# MAIN.net
KiCad netlist of a schematic drawn in Altium Designer
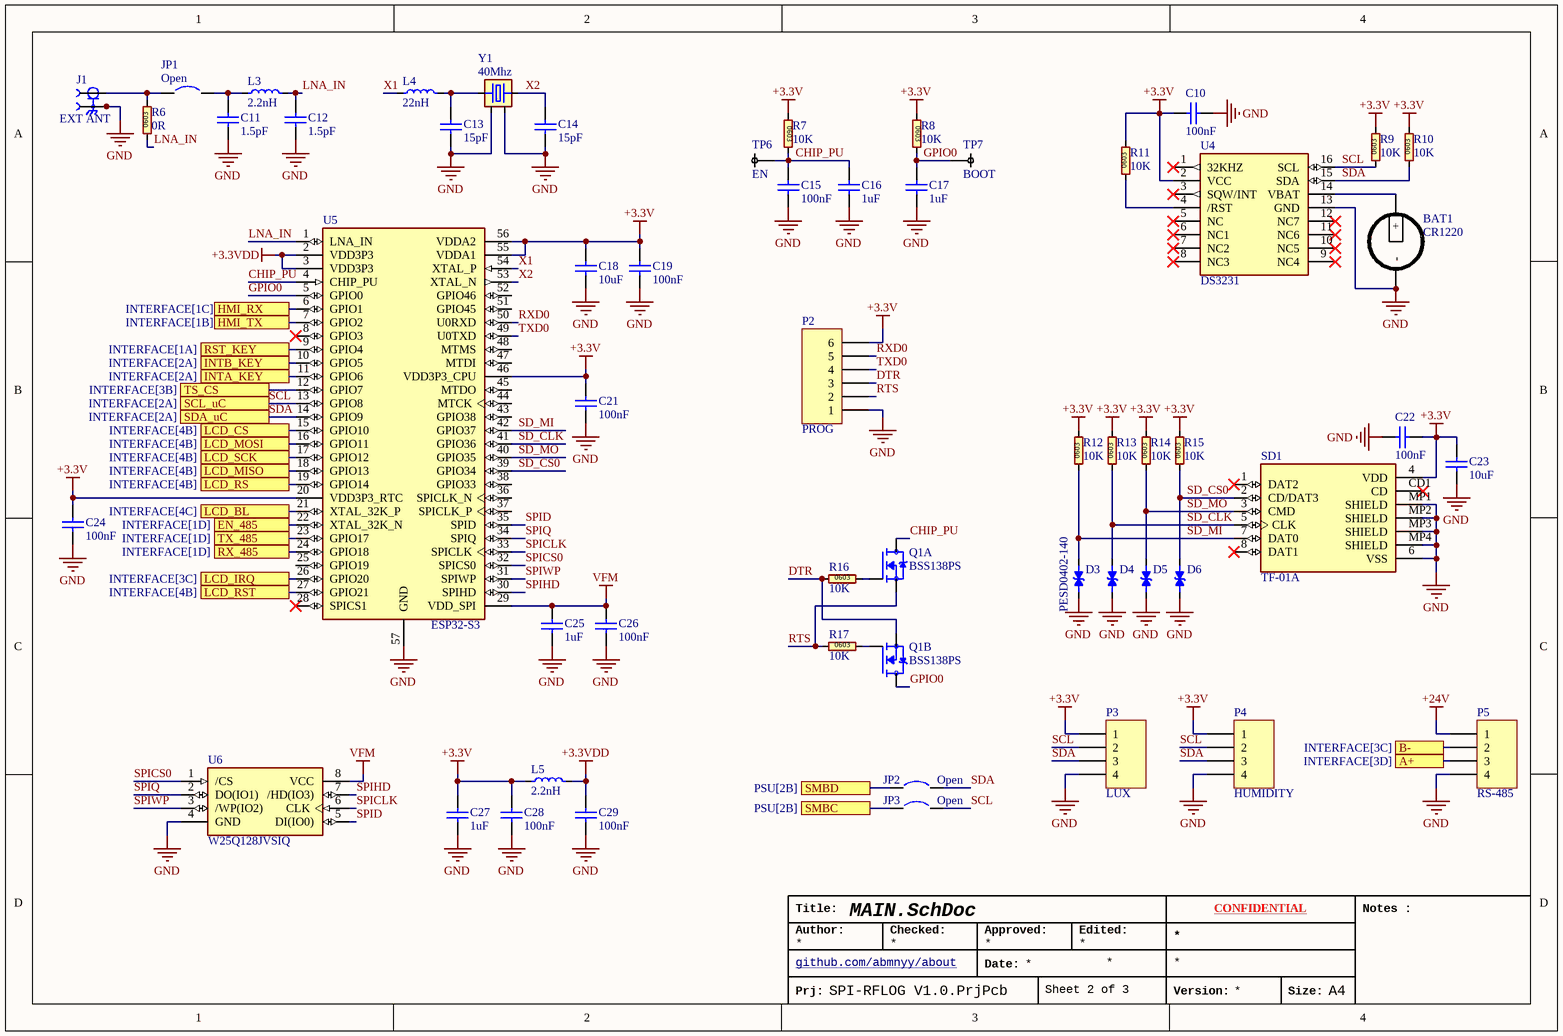
[diagram p0: MAIN.SchDoc]

(export (version "E")
  (design (tool "Eeschema 10.0.6"))
  (components
    (comp (ref "BAT1")
      (value "CR1220")
      (footprint "MPD_BC501SM-TR")
      (description "BATTERY HOLDER")
      (fields (field (name "MFR.PART #") "BC501SM") (field (name "LCSC PART #") "C5439670"))
      (libsource (lib "AB_SF") (part "CR1220 HOLDER"))
    )
    (comp (ref "C10")
      (value "100nF")
      (footprint "C0603")
      (description "0603 SMD Non-Polarity Capacitor")
      (libsource (lib "AB_SF") (part "Capacitor 0603 (Inch)"))
    )
    (comp (ref "C11")
      (value "1.5pF")
      (footprint "C0603")
      (description "0603 SMD Non-Polarity Capacitor")
      (fields (field (name "MFR.PART #") "CC0603CRNPO9BN1R5") (field (name "LCSC PART #") "C163551"))
      (libsource (lib "AB_SF") (part "Capacitor 0603 (Inch)"))
    )
    (comp (ref "C12")
      (value "1.5pF")
      (footprint "C0603")
      (description "0603 SMD Non-Polarity Capacitor")
      (fields (field (name "MFR.PART #") "CC0603CRNPO9BN1R5") (field (name "LCSC PART #") "C163551"))
      (libsource (lib "AB_SF") (part "Capacitor 0603 (Inch)"))
    )
    (comp (ref "C13")
      (value "15pF")
      (footprint "C0603")
      (description "0603 SMD Non-Polarity Capacitor")
      (fields (field (name "MFR.PART #") "X322540MPB4SI") (field (name "LCSC PART #") "C9010"))
      (libsource (lib "AB_SF") (part "Capacitor 0603 (Inch)"))
    )
    (comp (ref "C14")
      (value "15pF")
      (footprint "C0603")
      (description "0603 SMD Non-Polarity Capacitor")
      (fields (field (name "MFR.PART #") "X322540MPB4SI") (field (name "LCSC PART #") "C9010"))
      (libsource (lib "AB_SF") (part "Capacitor 0603 (Inch)"))
    )
    (comp (ref "C15")
      (value "100nF")
      (footprint "C0603")
      (description "0603 SMD Non-Polarity Capacitor")
      (libsource (lib "AB_SF") (part "Capacitor 0603 (Inch)"))
    )
    (comp (ref "C16")
      (value "1uF")
      (footprint "C0603")
      (description "0603 SMD Non-Polarity Capacitor")
      (fields (field (name "MFR.PART #") "CC0603KRX7R7BB105") (field (name "LCSC PART #") "C106248"))
      (libsource (lib "AB_SF") (part "Capacitor 0603 (Inch)"))
    )
    (comp (ref "C17")
      (value "1uF")
      (footprint "C0603")
      (description "0603 SMD Non-Polarity Capacitor")
      (fields (field (name "MFR.PART #") "CC0603KRX7R7BB105") (field (name "LCSC PART #") "C106248"))
      (libsource (lib "AB_SF") (part "Capacitor 0603 (Inch)"))
    )
    (comp (ref "C18")
      (value "10uF")
      (footprint "C0603")
      (description "0603 SMD Non-Polarity Capacitor")
      (fields (field (name "MFR.PART #") "CC0603MRX5R7BB106") (field (name "LCSC PART #") "C109457"))
      (libsource (lib "AB_SF") (part "Capacitor 0603 (Inch)"))
    )
    (comp (ref "C19")
      (value "100nF")
      (footprint "C0603")
      (description "0603 SMD Non-Polarity Capacitor")
      (libsource (lib "AB_SF") (part "Capacitor 0603 (Inch)"))
    )
    (comp (ref "C21")
      (value "100nF")
      (footprint "C0603")
      (description "0603 SMD Non-Polarity Capacitor")
      (libsource (lib "AB_SF") (part "Capacitor 0603 (Inch)"))
    )
    (comp (ref "C22")
      (value "100nF")
      (footprint "C0603")
      (description "0603 SMD Non-Polarity Capacitor")
      (libsource (lib "AB_SF") (part "Capacitor 0603 (Inch)"))
    )
    (comp (ref "C23")
      (value "10uF")
      (footprint "C0603")
      (description "0603 SMD Non-Polarity Capacitor")
      (libsource (lib "AB_SF") (part "Capacitor 0603 (Inch)"))
    )
    (comp (ref "C24")
      (value "100nF")
      (footprint "C0603")
      (description "0603 SMD Non-Polarity Capacitor")
      (libsource (lib "AB_SF") (part "Capacitor 0603 (Inch)"))
    )
    (comp (ref "C25")
      (value "1uF")
      (footprint "C0603")
      (description "0603 SMD Non-Polarity Capacitor")
      (libsource (lib "AB_SF") (part "Capacitor 0603 (Inch)"))
    )
    (comp (ref "C26")
      (value "100nF")
      (footprint "C0603")
      (description "0603 SMD Non-Polarity Capacitor")
      (libsource (lib "AB_SF") (part "Capacitor 0603 (Inch)"))
    )
    (comp (ref "C27")
      (value "1uF")
      (footprint "C0603")
      (description "0603 SMD Non-Polarity Capacitor")
      (libsource (lib "AB_SF") (part "Capacitor 0603 (Inch)"))
    )
    (comp (ref "C28")
      (value "100nF")
      (footprint "C0603")
      (description "0603 SMD Non-Polarity Capacitor")
      (libsource (lib "AB_SF") (part "Capacitor 0603 (Inch)"))
    )
    (comp (ref "C29")
      (value "100nF")
      (footprint "C0603")
      (description "0603 SMD Non-Polarity Capacitor")
      (libsource (lib "AB_SF") (part "Capacitor 0603 (Inch)"))
    )
    (comp (ref "D3")
      (value "PESD0402-140")
      (footprint "ESD0402")
      (description "40V Bidirectional 14V 0402 ESD and Surge Protection (TVS/ESD) ROHS")
      (fields (field (name "LCSC PART #") "C10662"))
      (libsource (lib "AB_SF") (part "PESD0402-140"))
    )
    (comp (ref "D4")
      (value "PESD0402-140")
      (footprint "ESD0402")
      (description "40V Bidirectional 14V 0402 ESD and Surge Protection (TVS/ESD) ROHS")
      (fields (field (name "LCSC PART #") "C10662"))
      (libsource (lib "AB_SF") (part "PESD0402-140"))
    )
    (comp (ref "D5")
      (value "PESD0402-140")
      (footprint "ESD0402")
      (description "40V Bidirectional 14V 0402 ESD and Surge Protection (TVS/ESD) ROHS")
      (fields (field (name "LCSC PART #") "C10662"))
      (libsource (lib "AB_SF") (part "PESD0402-140"))
    )
    (comp (ref "D6")
      (value "PESD0402-140")
      (footprint "ESD0402")
      (description "40V Bidirectional 14V 0402 ESD and Surge Protection (TVS/ESD) ROHS")
      (fields (field (name "LCSC PART #") "C10662"))
      (libsource (lib "AB_SF") (part "PESD0402-140"))
    )
    (comp (ref "J1")
      (value "EXT ANT")
      (footprint "IPEX_UF.L")
      (fields (field (name "MFR.PART #") "KH-IPEX-K501-29") (field (name "LCSC PART #") "C411563"))
      (libsource (lib "AB_SF") (part "IPEX UF.L"))
    )
    (comp (ref "JP1")
      (value "Open")
      (footprint "SB_STM")
      (description "Jumper Solder Pad")
      (fields (field (name "PUBLISHER") "Altium Limited"))
      (libsource (lib "AB_SF") (part "Jumper Solder"))
    )
    (comp (ref "JP2")
      (value "Open")
      (footprint "SB_STM")
      (description "Jumper Solder Pad")
      (fields (field (name "PUBLISHER") "Altium Limited"))
      (libsource (lib "AB_SF") (part "Jumper Solder"))
    )
    (comp (ref "JP3")
      (value "Open")
      (footprint "SB_STM")
      (description "Jumper Solder Pad")
      (fields (field (name "PUBLISHER") "Altium Limited"))
      (libsource (lib "AB_SF") (part "Jumper Solder"))
    )
    (comp (ref "L3")
      (value "2.2nH")
      (footprint "L0603")
      (description "Inductor with Package: 0603 Inch")
      (libsource (lib "AB_SF") (part "INDUCTOR 0603"))
    )
    (comp (ref "L4")
      (value "22nH")
      (footprint "L0603")
      (description "Inductor with Package: 0603 Inch")
      (fields (field (name "MFR.PART #") "VHF160808H22NJT") (field (name "LCSC PART #") "C90207"))
      (libsource (lib "AB_SF") (part "INDUCTOR 0603"))
    )
    (comp (ref "L5")
      (value "2.2nH")
      (footprint "L0603")
      (description "Inductor with Package: 0603 Inch")
      (fields (field (name "MFR.PART #") "LQW18AN2N2C80D") (field (name "LCSC PART #") "C71648"))
      (libsource (lib "AB_SF") (part "INDUCTOR 0603"))
    )
    (comp (ref "P2")
      (value "PROG")
      (footprint "HDR-6P-2.54mm")
      (description "Header, 6-Pin")
      (fields (field (name "PUBLISHER") "Altium Limited"))
      (libsource (lib "AB_SF") (part "Header 6"))
    )
    (comp (ref "P3")
      (value "LUX")
      (footprint "JST_XH-2.54")
      (description "CONNECTOR HEADER")
      (fields (field (name "PUBLISHER") "Altium Limited"))
      (libsource (lib "AB_SF") (part "Connector 4P"))
    )
    (comp (ref "P4")
      (value "HUMIDITY")
      (footprint "JST_XH-2.54")
      (description "CONNECTOR HEADER")
      (fields (field (name "PUBLISHER") "Altium Limited"))
      (libsource (lib "AB_SF") (part "Connector 4P"))
    )
    (comp (ref "P5")
      (value "RS-485")
      (footprint "JST_XH-2.54")
      (description "CONNECTOR HEADER")
      (fields (field (name "PUBLISHER") "Altium Limited"))
      (libsource (lib "AB_SF") (part "Connector 4P"))
    )
    (comp (ref "Q1")
      (value "BSS138PS")
      (footprint "SOT-363")
      (description "60 V, 320 mA dual N-channel Trench MOSFET")
      (fields (field (name "MFR.PART #") "BSS138PS,115") (field (name "LCSC PART #") "C193381"))
      (libsource (lib "AB_SF") (part "BSS138PS"))
    )
    (comp (ref "R6")
      (value "0R")
      (footprint "R0603")
      (description "0603 SMD Thick Resistor")
      (fields (field (name "MFR.PART #") "AC0603FR-070RL") (field (name "LCSC PART #") "C116699"))
      (libsource (lib "") (part "Resistor 0603 (Inch)_1"))
    )
    (comp (ref "R7")
      (value "10K")
      (footprint "R0603")
      (description "0603 SMD Thick Resistor")
      (libsource (lib "AB_SF") (part "Resistor 0603 (Inch)"))
    )
    (comp (ref "R8")
      (value "10K")
      (footprint "R0603")
      (description "0603 SMD Thick Resistor")
      (libsource (lib "AB_SF") (part "Resistor 0603 (Inch)"))
    )
    (comp (ref "R9")
      (value "10K")
      (footprint "R0603")
      (description "0603 SMD Thick Resistor")
      (libsource (lib "") (part "Resistor 0603 (Inch)_1"))
    )
    (comp (ref "R10")
      (value "10K")
      (footprint "R0603")
      (description "0603 SMD Thick Resistor")
      (libsource (lib "") (part "Resistor 0603 (Inch)_1"))
    )
    (comp (ref "R11")
      (value "10K")
      (footprint "R0603")
      (description "0603 SMD Thick Resistor")
      (libsource (lib "") (part "Resistor 0603 (Inch)_1"))
    )
    (comp (ref "R12")
      (value "10K")
      (footprint "R0603")
      (description "0603 SMD Thick Resistor")
      (libsource (lib "") (part "Resistor 0603 (Inch)_1"))
    )
    (comp (ref "R13")
      (value "10K")
      (footprint "R0603")
      (description "0603 SMD Thick Resistor")
      (libsource (lib "") (part "Resistor 0603 (Inch)_1"))
    )
    (comp (ref "R14")
      (value "10K")
      (footprint "R0603")
      (description "0603 SMD Thick Resistor")
      (libsource (lib "") (part "Resistor 0603 (Inch)_1"))
    )
    (comp (ref "R15")
      (value "10K")
      (footprint "R0603")
      (description "0603 SMD Thick Resistor")
      (libsource (lib "") (part "Resistor 0603 (Inch)_1"))
    )
    (comp (ref "R16")
      (value "10K")
      (footprint "R0603")
      (description "0603 SMD Thick Resistor")
      (libsource (lib "") (part "Resistor 0603 (Inch)_2"))
    )
    (comp (ref "R17")
      (value "10K")
      (footprint "R0603")
      (description "0603 SMD Thick Resistor")
      (libsource (lib "") (part "Resistor 0603 (Inch)_2"))
    )
    (comp (ref "SD1")
      (value "TF-01A")
      (footprint "TF-01A")
      (description "Standard Card Edge Connectors")
      (fields (field (name "LCSC PART #") "C2889258"))
      (libsource (lib "AB_SF") (part "TF-01A"))
    )
    (comp (ref "TP6")
      (value "EN")
      (footprint "PAD")
      (description "Thick Pad")
      (libsource (lib "AB_SF") (part "Test Point"))
    )
    (comp (ref "TP7")
      (value "BOOT")
      (footprint "PAD")
      (description "Thick Pad")
      (libsource (lib "AB_SF") (part "Test Point"))
    )
    (comp (ref "U4")
      (value "DS3231")
      (footprint "SOIC-16-WIDE")
      (description "Real Time Clock (RTC) IC Clock/Calendar - IÂ²C, 2-Wire Serial 8-SOIC (0.154, 3.90mm Width)")
      (fields (field (name "MFR.PART #") "DS3231SN#T&R") (field (name "LCSC PART #") "C9866"))
      (libsource (lib "AB_SF") (part "DS3231"))
    )
    (comp (ref "U5")
      (value "ESP32-S3")
      (footprint "ESP32-S3")
      (fields (field (name "MFR.PART #") "ESP32-S3R8") (field (name "LCSC PART #") "C2913194"))
      (libsource (lib "AB_SF") (part "ESP32-S3"))
    )
    (comp (ref "U6")
      (value "W25Q128JVSIQ")
      (footprint "SOIC-8-208miL")
      (description "FLASH - NOR Memory IC 128Mb (16M x 8) SPI - Quad I/O, QPI, DTR 133 MHz 8-SOIC")
      (fields (field (name "LCSC PART #") "C97521"))
      (libsource (lib "AB_SF") (part "W25Q128JVSIQ"))
    )
    (comp (ref "Y1")
      (value "40Mhz")
      (footprint "OSC_SMD3225-4")
      (description "40MHz Crystal Oscillator 15pF ±10ppm ±20ppm SMD3225-4P Crystals ROHS")
      (fields (field (name "MFR.PART #") "X322540MPB4SI") (field (name "LCSC PART #") "C9010"))
      (libsource (lib "AB_SF") (part "XTAL-40Mhz"))
    )
  )
  (nets
    (net (code "1") (name "+3.3V") (class "Default")
      (node (ref "C10") (pin "2") (pinfunction "2_2") (pintype "passive"))
      (node (ref "C18") (pin "2") (pinfunction "2_2") (pintype "passive"))
      (node (ref "C19") (pin "2") (pinfunction "2_2") (pintype "passive"))
      (node (ref "C21") (pin "2") (pinfunction "2_2") (pintype "passive"))
      (node (ref "C22") (pin "1") (pinfunction "1_1") (pintype "passive"))
      (node (ref "C23") (pin "2") (pinfunction "2_2") (pintype "passive"))
      (node (ref "C24") (pin "2") (pinfunction "2_2") (pintype "passive"))
      (node (ref "C27") (pin "2") (pinfunction "2_2") (pintype "passive"))
      (node (ref "C28") (pin "2") (pinfunction "2_2") (pintype "passive"))
      (node (ref "L5") (pin "1") (pinfunction "1_1") (pintype "passive"))
      (node (ref "P2") (pin "6") (pinfunction "6_6") (pintype "passive"))
      (node (ref "P3") (pin "1") (pinfunction "1_1") (pintype "passive"))
      (node (ref "P4") (pin "1") (pinfunction "1_1") (pintype "passive"))
      (node (ref "R10") (pin "2") (pinfunction "2_2") (pintype "passive"))
      (node (ref "R11") (pin "2") (pinfunction "2_2") (pintype "passive"))
      (node (ref "R12") (pin "2") (pinfunction "2_2") (pintype "passive"))
      (node (ref "R13") (pin "2") (pinfunction "2_2") (pintype "passive"))
      (node (ref "R14") (pin "2") (pinfunction "2_2") (pintype "passive"))
      (node (ref "R15") (pin "2") (pinfunction "2_2") (pintype "passive"))
      (node (ref "R7") (pin "1") (pinfunction "1_1") (pintype "passive"))
      (node (ref "R8") (pin "1") (pinfunction "1_1") (pintype "passive"))
      (node (ref "R9") (pin "2") (pinfunction "2_2") (pintype "passive"))
      (node (ref "SD1") (pin "4") (pinfunction "VDD_4") (pintype "power_in"))
      (node (ref "U4") (pin "2") (pinfunction "VCC_2") (pintype "power_in"))
      (node (ref "U5") (pin "20") (pinfunction "VDD3P3_RTC_20") (pintype "power_in"))
      (node (ref "U5") (pin "46") (pinfunction "VDD3P3_CPU_46") (pintype "power_in"))
      (node (ref "U5") (pin "55") (pinfunction "VDDA1_55") (pintype "power_in"))
      (node (ref "U5") (pin "56") (pinfunction "VDDA2_56") (pintype "power_in"))
    )
    (net (code "2") (name "+3.3VDD") (class "Default")
      (node (ref "C29") (pin "2") (pinfunction "2_2") (pintype "passive"))
      (node (ref "L5") (pin "2") (pinfunction "2_2") (pintype "passive"))
      (node (ref "U5") (pin "2") (pinfunction "VDD3P3_2") (pintype "power_in"))
      (node (ref "U5") (pin "3") (pinfunction "VDD3P3_3") (pintype "power_in"))
    )
    (net (code "3") (name "+24V") (class "Default")
      (node (ref "P5") (pin "1") (pinfunction "1_1") (pintype "passive"))
    )
    (net (code "4") (name "/A+") (class "Default")
      (node (ref "P5") (pin "3") (pinfunction "3_3") (pintype "passive"))
    )
    (net (code "5") (name "/B-") (class "Default")
      (node (ref "P5") (pin "2") (pinfunction "2_2") (pintype "passive"))
    )
    (net (code "6") (name "/CHIP_PU") (class "Default")
      (node (ref "C15") (pin "1") (pinfunction "1_1") (pintype "passive"))
      (node (ref "C16") (pin "1") (pinfunction "1_1") (pintype "passive"))
      (node (ref "Q1") (pin "6") (pinfunction "D1_6") (pintype "passive"))
      (node (ref "R7") (pin "2") (pinfunction "2_2") (pintype "passive"))
      (node (ref "TP6") (pin "1") (pinfunction "1_1") (pintype "passive"))
      (node (ref "U5") (pin "4") (pinfunction "CHIP_PU_4") (pintype "input"))
    )
    (net (code "7") (name "/DTR") (class "Default")
      (node (ref "P2") (pin "3") (pinfunction "3_3") (pintype "passive"))
      (node (ref "Q1") (pin "4") (pinfunction "S2_4") (pintype "passive"))
      (node (ref "R16") (pin "1") (pinfunction "1_1") (pintype "passive"))
    )
    (net (code "8") (name "/EN_485") (class "Default")
      (node (ref "U5") (pin "22") (pinfunction "XTAL_32K_N_22") (pintype "bidirectional"))
    )
    (net (code "9") (name "/GPIO0") (class "Default")
      (node (ref "C17") (pin "1") (pinfunction "1_1") (pintype "passive"))
      (node (ref "Q1") (pin "3") (pinfunction "D2_3") (pintype "passive"))
      (node (ref "R8") (pin "2") (pinfunction "2_2") (pintype "passive"))
      (node (ref "TP7") (pin "1") (pinfunction "1_1") (pintype "passive"))
      (node (ref "U5") (pin "5") (pinfunction "GPIO0_5") (pintype "bidirectional"))
    )
    (net (code "10") (name "/HMI_RX") (class "Default")
      (node (ref "U5") (pin "6") (pinfunction "GPIO1_6") (pintype "bidirectional"))
    )
    (net (code "11") (name "/HMI_TX") (class "Default")
      (node (ref "U5") (pin "7") (pinfunction "GPIO2_7") (pintype "bidirectional"))
    )
    (net (code "12") (name "/INTA_KEY") (class "Default")
      (node (ref "U5") (pin "11") (pinfunction "GPIO6_11") (pintype "bidirectional"))
    )
    (net (code "13") (name "/INTB_KEY") (class "Default")
      (node (ref "U5") (pin "10") (pinfunction "GPIO5_10") (pintype "bidirectional"))
    )
    (net (code "14") (name "/LCD_BL") (class "Default")
      (node (ref "U5") (pin "21") (pinfunction "XTAL_32K_P_21") (pintype "bidirectional"))
    )
    (net (code "15") (name "/LCD_CS") (class "Default")
      (node (ref "U5") (pin "15") (pinfunction "GPIO10_15") (pintype "bidirectional"))
    )
    (net (code "16") (name "/LCD_IRQ") (class "Default")
      (node (ref "U5") (pin "26") (pinfunction "GPIO20_26") (pintype "bidirectional"))
    )
    (net (code "17") (name "/LCD_MISO") (class "Default")
      (node (ref "U5") (pin "18") (pinfunction "GPIO13_18") (pintype "bidirectional"))
    )
    (net (code "18") (name "/LCD_MOSI") (class "Default")
      (node (ref "U5") (pin "16") (pinfunction "GPIO11_16") (pintype "bidirectional"))
    )
    (net (code "19") (name "/LCD_RS") (class "Default")
      (node (ref "U5") (pin "19") (pinfunction "GPIO14_19") (pintype "bidirectional"))
    )
    (net (code "20") (name "/LCD_RST") (class "Default")
      (node (ref "U5") (pin "27") (pinfunction "GPIO21_27") (pintype "bidirectional"))
    )
    (net (code "21") (name "/LCD_SCK") (class "Default")
      (node (ref "U5") (pin "17") (pinfunction "GPIO12_17") (pintype "bidirectional"))
    )
    (net (code "22") (name "/LNA_IN") (class "Default")
      (node (ref "C12") (pin "2") (pinfunction "2_2") (pintype "passive"))
      (node (ref "L3") (pin "2") (pinfunction "2_2") (pintype "passive"))
      (node (ref "R6") (pin "1") (pinfunction "1_1") (pintype "passive"))
      (node (ref "U5") (pin "1") (pinfunction "LNA_IN_1") (pintype "bidirectional"))
    )
    (net (code "23") (name "/RST_KEY") (class "Default")
      (node (ref "U5") (pin "9") (pinfunction "GPIO4_9") (pintype "bidirectional"))
    )
    (net (code "24") (name "/RTS") (class "Default")
      (node (ref "P2") (pin "2") (pinfunction "2_2") (pintype "passive"))
      (node (ref "Q1") (pin "1") (pinfunction "S1_1") (pintype "passive"))
      (node (ref "R17") (pin "1") (pinfunction "1_1") (pintype "passive"))
    )
    (net (code "25") (name "/RXD0") (class "Default")
      (node (ref "P2") (pin "5") (pinfunction "5_5") (pintype "passive"))
      (node (ref "U5") (pin "50") (pinfunction "U0RXD_50") (pintype "bidirectional"))
    )
    (net (code "26") (name "/RX_485") (class "Default")
      (node (ref "U5") (pin "24") (pinfunction "GPIO18_24") (pintype "bidirectional"))
    )
    (net (code "27") (name "/SCL") (class "Default")
      (node (ref "JP3") (pin "2") (pinfunction "2_2") (pintype "passive"))
      (node (ref "P3") (pin "2") (pinfunction "2_2") (pintype "passive"))
      (node (ref "P4") (pin "2") (pinfunction "2_2") (pintype "passive"))
      (node (ref "R9") (pin "1") (pinfunction "1_1") (pintype "passive"))
      (node (ref "U4") (pin "16") (pinfunction "SCL_16") (pintype "bidirectional"))
      (node (ref "U5") (pin "13") (pinfunction "GPIO8_13") (pintype "bidirectional"))
    )
    (net (code "28") (name "/SDA") (class "Default")
      (node (ref "JP2") (pin "2") (pinfunction "2_2") (pintype "passive"))
      (node (ref "P3") (pin "3") (pinfunction "3_3") (pintype "passive"))
      (node (ref "P4") (pin "3") (pinfunction "3_3") (pintype "passive"))
      (node (ref "R10") (pin "1") (pinfunction "1_1") (pintype "passive"))
      (node (ref "U4") (pin "15") (pinfunction "SDA_15") (pintype "bidirectional"))
      (node (ref "U5") (pin "14") (pinfunction "GPIO9_14") (pintype "bidirectional"))
    )
    (net (code "29") (name "/SD_CLK") (class "Default")
      (node (ref "D4") (pin "2") (pinfunction "2_2") (pintype "passive"))
      (node (ref "R13") (pin "1") (pinfunction "1_1") (pintype "passive"))
      (node (ref "SD1") (pin "5") (pinfunction "CLK_5") (pintype "bidirectional"))
      (node (ref "U5") (pin "41") (pinfunction "GPIO36_41") (pintype "bidirectional"))
    )
    (net (code "30") (name "/SD_CS0") (class "Default")
      (node (ref "D6") (pin "2") (pinfunction "2_2") (pintype "passive"))
      (node (ref "R15") (pin "1") (pinfunction "1_1") (pintype "passive"))
      (node (ref "SD1") (pin "2") (pinfunction "CD/DAT3_2") (pintype "bidirectional"))
      (node (ref "U5") (pin "39") (pinfunction "GPIO34_39") (pintype "bidirectional"))
    )
    (net (code "31") (name "/SD_MI") (class "Default")
      (node (ref "D3") (pin "2") (pinfunction "2_2") (pintype "passive"))
      (node (ref "R12") (pin "1") (pinfunction "1_1") (pintype "passive"))
      (node (ref "SD1") (pin "7") (pinfunction "DAT0_7") (pintype "bidirectional"))
      (node (ref "U5") (pin "42") (pinfunction "GPIO37_42") (pintype "bidirectional"))
    )
    (net (code "32") (name "/SD_MO") (class "Default")
      (node (ref "D5") (pin "2") (pinfunction "2_2") (pintype "passive"))
      (node (ref "R14") (pin "1") (pinfunction "1_1") (pintype "passive"))
      (node (ref "SD1") (pin "3") (pinfunction "CMD_3") (pintype "bidirectional"))
      (node (ref "U5") (pin "40") (pinfunction "GPIO35_40") (pintype "bidirectional"))
    )
    (net (code "33") (name "/SMBC") (class "Default")
      (node (ref "JP3") (pin "1") (pinfunction "1_1") (pintype "passive"))
    )
    (net (code "34") (name "/SMBD") (class "Default")
      (node (ref "JP2") (pin "1") (pinfunction "1_1") (pintype "passive"))
    )
    (net (code "35") (name "/SPICLK") (class "Default")
      (node (ref "U5") (pin "33") (pinfunction "SPICLK_33") (pintype "bidirectional"))
      (node (ref "U6") (pin "6") (pinfunction "CLK_6") (pintype "input"))
    )
    (net (code "36") (name "/SPICS0") (class "Default")
      (node (ref "U5") (pin "32") (pinfunction "SPICS0_32") (pintype "bidirectional"))
      (node (ref "U6") (pin "1") (pinfunction "/CS_1") (pintype "input"))
    )
    (net (code "37") (name "/SPID") (class "Default")
      (node (ref "U5") (pin "35") (pinfunction "SPID_35") (pintype "bidirectional"))
      (node (ref "U6") (pin "5") (pinfunction "DI(IO0)_5") (pintype "bidirectional"))
    )
    (net (code "38") (name "/SPIHD") (class "Default")
      (node (ref "U5") (pin "30") (pinfunction "SPIHD_30") (pintype "bidirectional"))
      (node (ref "U6") (pin "7") (pinfunction "/HD(IO3)_7") (pintype "bidirectional"))
    )
    (net (code "39") (name "/SPIQ") (class "Default")
      (node (ref "U5") (pin "34") (pinfunction "SPIQ_34") (pintype "bidirectional"))
      (node (ref "U6") (pin "2") (pinfunction "DO(IO1)_2") (pintype "bidirectional"))
    )
    (net (code "40") (name "/SPIWP") (class "Default")
      (node (ref "U5") (pin "31") (pinfunction "SPIWP_31") (pintype "bidirectional"))
      (node (ref "U6") (pin "3") (pinfunction "/WP(IO2)_3") (pintype "bidirectional"))
    )
    (net (code "41") (name "/TS_CS") (class "Default")
      (node (ref "U5") (pin "12") (pinfunction "GPIO7_12") (pintype "bidirectional"))
    )
    (net (code "42") (name "/TXD0") (class "Default")
      (node (ref "P2") (pin "4") (pinfunction "4_4") (pintype "passive"))
      (node (ref "U5") (pin "49") (pinfunction "U0TXD_49") (pintype "bidirectional"))
    )
    (net (code "43") (name "/TX_485") (class "Default")
      (node (ref "U5") (pin "23") (pinfunction "GPIO17_23") (pintype "bidirectional"))
    )
    (net (code "44") (name "/X1") (class "Default")
      (node (ref "L4") (pin "1") (pinfunction "1_1") (pintype "passive"))
      (node (ref "U5") (pin "54") (pinfunction "XTAL_P_54") (pintype "input"))
    )
    (net (code "45") (name "/X2") (class "Default")
      (node (ref "C14") (pin "2") (pinfunction "2_2") (pintype "passive"))
      (node (ref "U5") (pin "53") (pinfunction "XTAL_N_53") (pintype "output"))
      (node (ref "Y1") (pin "3") (pinfunction "OSC2_3") (pintype "passive"))
    )
    (net (code "46") (name "GND") (class "Default")
      (node (ref "BAT1") (pin "-") (pinfunction "-_-") (pintype "passive"))
      (node (ref "C10") (pin "1") (pinfunction "1_1") (pintype "passive"))
      (node (ref "C11") (pin "1") (pinfunction "1_1") (pintype "passive"))
      (node (ref "C12") (pin "1") (pinfunction "1_1") (pintype "passive"))
      (node (ref "C13") (pin "1") (pinfunction "1_1") (pintype "passive"))
      (node (ref "C14") (pin "1") (pinfunction "1_1") (pintype "passive"))
      (node (ref "C15") (pin "2") (pinfunction "2_2") (pintype "passive"))
      (node (ref "C16") (pin "2") (pinfunction "2_2") (pintype "passive"))
      (node (ref "C17") (pin "2") (pinfunction "2_2") (pintype "passive"))
      (node (ref "C18") (pin "1") (pinfunction "1_1") (pintype "passive"))
      (node (ref "C19") (pin "1") (pinfunction "1_1") (pintype "passive"))
      (node (ref "C21") (pin "1") (pinfunction "1_1") (pintype "passive"))
      (node (ref "C22") (pin "2") (pinfunction "2_2") (pintype "passive"))
      (node (ref "C23") (pin "1") (pinfunction "1_1") (pintype "passive"))
      (node (ref "C24") (pin "1") (pinfunction "1_1") (pintype "passive"))
      (node (ref "C25") (pin "1") (pinfunction "1_1") (pintype "passive"))
      (node (ref "C26") (pin "1") (pinfunction "1_1") (pintype "passive"))
      (node (ref "C27") (pin "1") (pinfunction "1_1") (pintype "passive"))
      (node (ref "C28") (pin "1") (pinfunction "1_1") (pintype "passive"))
      (node (ref "C29") (pin "1") (pinfunction "1_1") (pintype "passive"))
      (node (ref "D3") (pin "1") (pinfunction "1_1") (pintype "passive"))
      (node (ref "D4") (pin "1") (pinfunction "1_1") (pintype "passive"))
      (node (ref "D5") (pin "1") (pinfunction "1_1") (pintype "passive"))
      (node (ref "D6") (pin "1") (pinfunction "1_1") (pintype "passive"))
      (node (ref "J1") (pin "2") (pinfunction "GROUND_2") (pintype "passive"))
      (node (ref "J1") (pin "3") (pinfunction "GROUND_3") (pintype "passive"))
      (node (ref "P2") (pin "1") (pinfunction "1_1") (pintype "passive"))
      (node (ref "P3") (pin "4") (pinfunction "4_4") (pintype "passive"))
      (node (ref "P4") (pin "4") (pinfunction "4_4") (pintype "passive"))
      (node (ref "P5") (pin "4") (pinfunction "4_4") (pintype "passive"))
      (node (ref "SD1") (pin "6") (pinfunction "VSS_6") (pintype "power_in"))
      (node (ref "SD1") (pin "MP1") (pinfunction "SHIELD_MP1") (pintype "power_in"))
      (node (ref "SD1") (pin "MP2") (pinfunction "SHIELD_MP2") (pintype "power_in"))
      (node (ref "SD1") (pin "MP3") (pinfunction "SHIELD_MP3") (pintype "power_in"))
      (node (ref "SD1") (pin "MP4") (pinfunction "SHIELD_MP4") (pintype "power_in"))
      (node (ref "U4") (pin "13") (pinfunction "GND_13") (pintype "power_in"))
      (node (ref "U5") (pin "57") (pinfunction "GND_57") (pintype "power_in"))
      (node (ref "U6") (pin "4") (pinfunction "GND_4") (pintype "power_in"))
      (node (ref "Y1") (pin "2") (pinfunction "GND_2") (pintype "passive"))
      (node (ref "Y1") (pin "4") (pinfunction "GND_4") (pintype "passive"))
    )
    (net (code "47") (name "Net-(C11-Pad2)") (class "Default")
      (node (ref "C11") (pin "2") (pinfunction "2_2") (pintype "passive"))
      (node (ref "JP1") (pin "2") (pinfunction "2_2") (pintype "passive"))
      (node (ref "L3") (pin "1") (pinfunction "1_1") (pintype "passive"))
    )
    (net (code "48") (name "Net-(J1-SIGNAL)") (class "Default")
      (node (ref "J1") (pin "1") (pinfunction "SIGNAL_1") (pintype "passive"))
      (node (ref "JP1") (pin "1") (pinfunction "1_1") (pintype "passive"))
      (node (ref "R6") (pin "2") (pinfunction "2_2") (pintype "passive"))
    )
    (net (code "49") (name "Net-(Q1A-G1)") (class "Default")
      (node (ref "Q1") (pin "2") (pinfunction "G1_2") (pintype "passive"))
      (node (ref "R16") (pin "2") (pinfunction "2_2") (pintype "passive"))
    )
    (net (code "50") (name "Net-(Q1B-G2)") (class "Default")
      (node (ref "Q1") (pin "5") (pinfunction "G2_5") (pintype "passive"))
      (node (ref "R17") (pin "2") (pinfunction "2_2") (pintype "passive"))
    )
    (net (code "51") (name "Net-(U4-VBAT)") (class "Default")
      (node (ref "BAT1") (pin "+") (pinfunction "+_+") (pintype "passive"))
      (node (ref "U4") (pin "14") (pinfunction "VBAT_14") (pintype "power_in"))
    )
    (net (code "52") (name "Net-(U4-{slash}RST)") (class "Default")
      (node (ref "R11") (pin "1") (pinfunction "1_1") (pintype "passive"))
      (node (ref "U4") (pin "4") (pinfunction "/RST_4") (pintype "passive"))
    )
    (net (code "53") (name "Net-(Y1-OSC1)") (class "Default")
      (node (ref "C13") (pin "2") (pinfunction "2_2") (pintype "passive"))
      (node (ref "L4") (pin "2") (pinfunction "2_2") (pintype "passive"))
      (node (ref "Y1") (pin "1") (pinfunction "OSC1_1") (pintype "passive"))
    )
    (net (code "54") (name "VFM") (class "Default")
      (node (ref "C25") (pin "2") (pinfunction "2_2") (pintype "passive"))
      (node (ref "C26") (pin "2") (pinfunction "2_2") (pintype "passive"))
      (node (ref "U5") (pin "29") (pinfunction "VDD_SPI_29") (pintype "power_in"))
      (node (ref "U6") (pin "8") (pinfunction "VCC_8") (pintype "power_in"))
    )
    (net (code "55") (name "unconnected-(SD1-CD-PadCD1)") (class "Default")
      (node (ref "SD1") (pin "CD1") (pinfunction "CD_CD1") (pintype "passive+no_connect"))
    )
    (net (code "56") (name "unconnected-(SD1-DAT1-Pad8)") (class "Default")
      (node (ref "SD1") (pin "8") (pinfunction "DAT1_8") (pintype "bidirectional+no_connect"))
    )
    (net (code "57") (name "unconnected-(SD1-DAT2-Pad1)") (class "Default")
      (node (ref "SD1") (pin "1") (pinfunction "DAT2_1") (pintype "bidirectional+no_connect"))
    )
    (net (code "58") (name "unconnected-(U4-32KHZ-Pad1)") (class "Default")
      (node (ref "U4") (pin "1") (pinfunction "32KHZ_1") (pintype "output+no_connect"))
    )
    (net (code "59") (name "unconnected-(U4-NC-Pad5)") (class "Default")
      (node (ref "U4") (pin "5") (pinfunction "NC_5") (pintype "passive+no_connect"))
    )
    (net (code "60") (name "unconnected-(U4-NC1-Pad6)") (class "Default")
      (node (ref "U4") (pin "6") (pinfunction "NC1_6") (pintype "passive+no_connect"))
    )
    (net (code "61") (name "unconnected-(U4-NC2-Pad7)") (class "Default")
      (node (ref "U4") (pin "7") (pinfunction "NC2_7") (pintype "passive+no_connect"))
    )
    (net (code "62") (name "unconnected-(U4-NC3-Pad8)") (class "Default")
      (node (ref "U4") (pin "8") (pinfunction "NC3_8") (pintype "passive+no_connect"))
    )
    (net (code "63") (name "unconnected-(U4-NC4-Pad9)") (class "Default")
      (node (ref "U4") (pin "9") (pinfunction "NC4_9") (pintype "passive+no_connect"))
    )
    (net (code "64") (name "unconnected-(U4-NC5-Pad10)") (class "Default")
      (node (ref "U4") (pin "10") (pinfunction "NC5_10") (pintype "passive+no_connect"))
    )
    (net (code "65") (name "unconnected-(U4-NC6-Pad11)") (class "Default")
      (node (ref "U4") (pin "11") (pinfunction "NC6_11") (pintype "passive+no_connect"))
    )
    (net (code "66") (name "unconnected-(U4-NC7-Pad12)") (class "Default")
      (node (ref "U4") (pin "12") (pinfunction "NC7_12") (pintype "passive+no_connect"))
    )
    (net (code "67") (name "unconnected-(U4-SQW{slash}INT-Pad3)") (class "Default")
      (node (ref "U4") (pin "3") (pinfunction "SQW/INT_3") (pintype "output+no_connect"))
    )
    (net (code "68") (name "unconnected-(U5-GPIO3-Pad8)") (class "Default")
      (node (ref "U5") (pin "8") (pinfunction "GPIO3_8") (pintype "bidirectional+no_connect"))
    )
    (net (code "69") (name "unconnected-(U5-GPIO19-Pad25)") (class "Default")
      (node (ref "U5") (pin "25") (pinfunction "GPIO19_25") (pintype "bidirectional"))
    )
    (net (code "70") (name "unconnected-(U5-GPIO33-Pad38)") (class "Default")
      (node (ref "U5") (pin "38") (pinfunction "GPIO33_38") (pintype "bidirectional"))
    )
    (net (code "71") (name "unconnected-(U5-GPIO38-Pad43)") (class "Default")
      (node (ref "U5") (pin "43") (pinfunction "GPIO38_43") (pintype "bidirectional"))
    )
    (net (code "72") (name "unconnected-(U5-GPIO45-Pad51)") (class "Default")
      (node (ref "U5") (pin "51") (pinfunction "GPIO45_51") (pintype "bidirectional"))
    )
    (net (code "73") (name "unconnected-(U5-GPIO46-Pad52)") (class "Default")
      (node (ref "U5") (pin "52") (pinfunction "GPIO46_52") (pintype "bidirectional"))
    )
    (net (code "74") (name "unconnected-(U5-MTCK-Pad44)") (class "Default")
      (node (ref "U5") (pin "44") (pinfunction "MTCK_44") (pintype "bidirectional"))
    )
    (net (code "75") (name "unconnected-(U5-MTDI-Pad47)") (class "Default")
      (node (ref "U5") (pin "47") (pinfunction "MTDI_47") (pintype "bidirectional"))
    )
    (net (code "76") (name "unconnected-(U5-MTDO-Pad45)") (class "Default")
      (node (ref "U5") (pin "45") (pinfunction "MTDO_45") (pintype "bidirectional"))
    )
    (net (code "77") (name "unconnected-(U5-MTMS-Pad48)") (class "Default")
      (node (ref "U5") (pin "48") (pinfunction "MTMS_48") (pintype "bidirectional"))
    )
    (net (code "78") (name "unconnected-(U5-SPICLK_N-Pad36)") (class "Default")
      (node (ref "U5") (pin "36") (pinfunction "SPICLK_N_36") (pintype "bidirectional"))
    )
    (net (code "79") (name "unconnected-(U5-SPICLK_P-Pad37)") (class "Default")
      (node (ref "U5") (pin "37") (pinfunction "SPICLK_P_37") (pintype "bidirectional"))
    )
    (net (code "80") (name "unconnected-(U5-SPICS1-Pad28)") (class "Default")
      (node (ref "U5") (pin "28") (pinfunction "SPICS1_28") (pintype "bidirectional+no_connect"))
    )
  )
)
